# UART_connect.net
KiCad netlist of a schematic drawn in Altium Designer
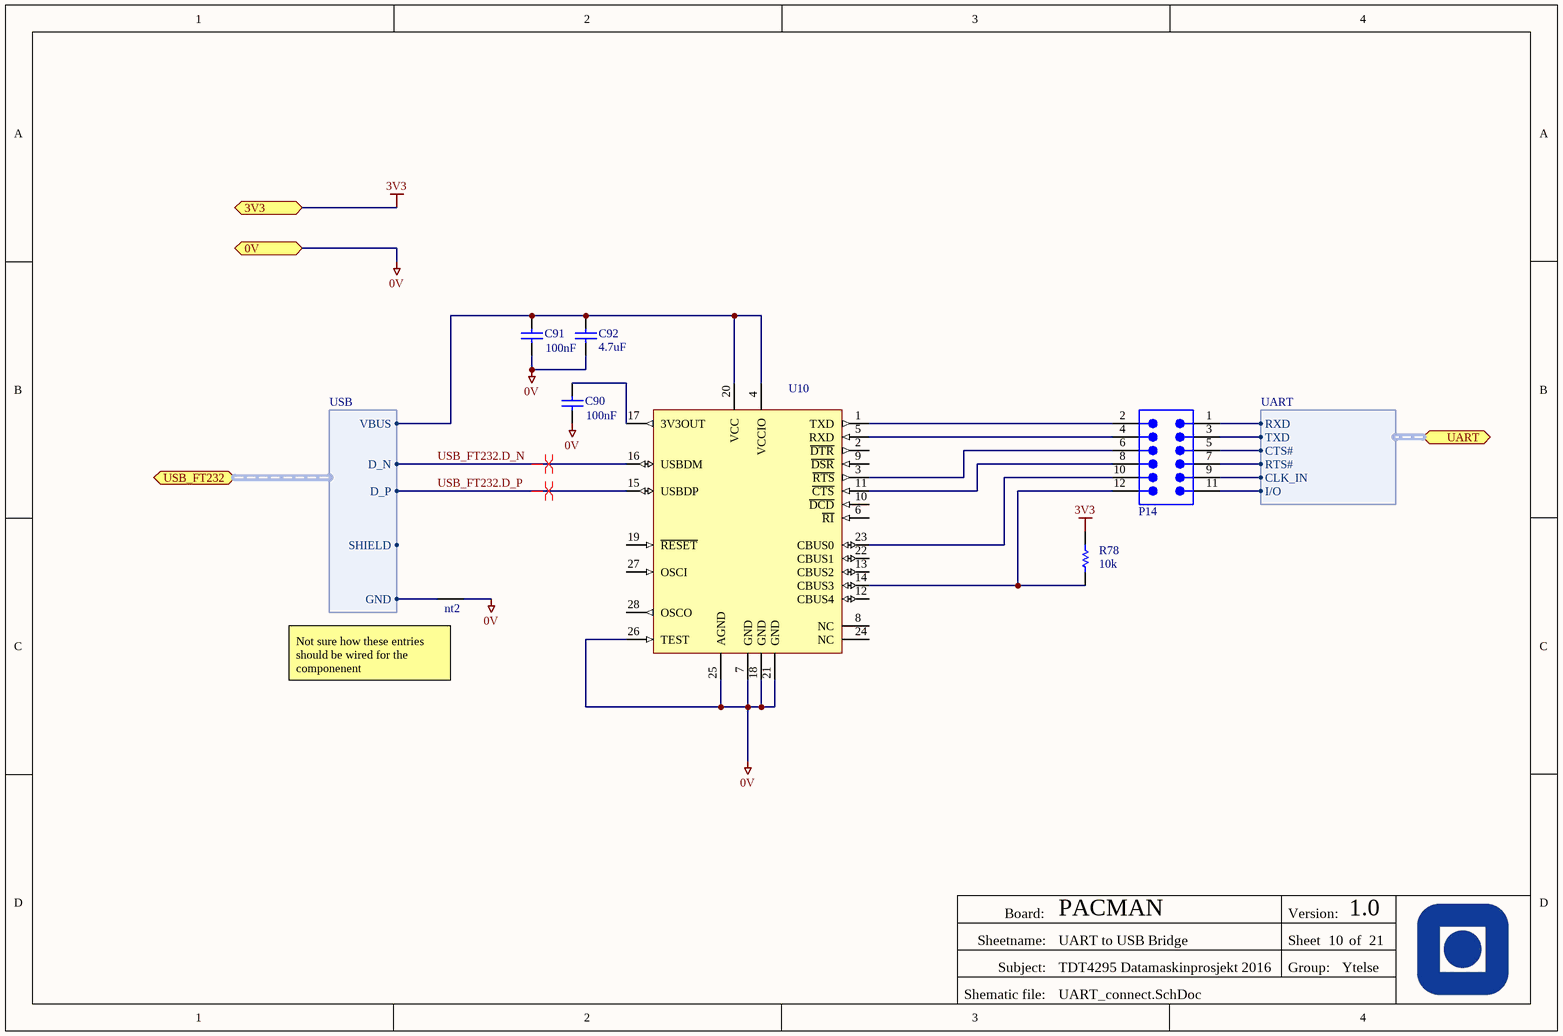
[diagram p0: UART_connect.SchDoc]

(export (version "E")
  (design (tool "Eeschema 10.0.6"))
  (components
    (comp (ref "C90")
      (value "100nF")
      (footprint "CAPC0603(1608)100_M")
      (description "CAP 100nF 16V ±5% 0603 (1608 Metric) Thickness 1mm SMD")
      (fields (field (name "TOLERANCE") "Â±5%") (field (name "Comment") "CAP 100nF 16V 0603(1608)"))
      (libsource (lib "Altium Content Vault") (part "CMP-1035-02583-1"))
    )
    (comp (ref "C91")
      (value "100nF")
      (footprint "CAPC0603(1608)100_M")
      (description "CAP 100nF 16V ±5% 0603 (1608 Metric) Thickness 1mm SMD")
      (fields (field (name "TOLERANCE") "Â±5%") (field (name "Comment") "CAP 100nF 16V 0603(1608)"))
      (libsource (lib "Altium Content Vault") (part "CMP-1035-02583-1"))
    )
    (comp (ref "C92")
      (value "4.7uF")
      (footprint "CAPC0603(1608)100_M")
      (description "CAP 4.7uF 16V ±10% 0603 (1608 Metric) Thickness 1mm SMD")
      (fields (field (name "TOLERANCE") "Â±10%") (field (name "Comment") "CAP 4.7uF 16V 0603(1608)"))
      (libsource (lib "Altium Content Vault") (part "CMP-1035-02788-1"))
    )
    (comp (ref "nt2")
      (value "net tie")
      (footprint "net tie")
      (description "used to connect nets without transferring net name")
      (libsource (lib "dmpro16lib") (part "net tie"))
    )
    (comp (ref "P14")
      (value "TSW-106-07-T-D")
      (footprint "SMTC-TSW-106-07-X-D")
      (fields (field (name "MANUFACTURER") "Samtec"))
      (libsource (lib "Altium Content Vault") (part "CMP-1024-00380-1"))
    )
    (comp (ref "R78")
      (value "10k")
      (footprint "RESC0603(1608)_N")
      (description "10K 0.1W 1% 0603 (1608 Metric)  SMD")
      (fields (field (name "POWER") "0.1 W") (field (name "TOLERANCE") "1 %"))
      (libsource (lib "Altium Content Vault") (part "CMP-1012-00623-1"))
    )
    (comp (ref "U10")
      (value "FT232RL-Reel")
      (footprint "SSOP-28_L")
      (description "USB UART Asynchronous Serial Data Transfer Chip, SSOP-28, Tape and Reel")
      (libsource (lib "Altium Content Vault") (part "CMP-0078-00029-1"))
    )
  )
  (nets
    (net (code "3") (name "/CLK_IN") (class "Default")
      (node (ref "P14") (pin "9") (pinfunction "9_9") (pintype "passive"))
    )
    (net (code "4") (name "/CTS#") (class "Default")
      (node (ref "P14") (pin "5") (pinfunction "5_5") (pintype "passive"))
    )
    (net (code "5") (name "/GND") (class "Default")
      (node (ref "nt2") (pin "0") (pinfunction "0_0") (pintype "passive"))
    )
    (net (code "6") (name "/I{slash}O") (class "Default")
      (node (ref "P14") (pin "11") (pinfunction "11_11") (pintype "passive"))
    )
    (net (code "7") (name "/RTS#") (class "Default")
      (node (ref "P14") (pin "7") (pinfunction "7_7") (pintype "passive"))
    )
    (net (code "8") (name "/RXD") (class "Default")
      (node (ref "P14") (pin "1") (pinfunction "1_1") (pintype "passive"))
    )
    (net (code "9") (name "/TXD") (class "Default")
      (node (ref "P14") (pin "3") (pinfunction "3_3") (pintype "passive"))
    )
    (net (code "10") (name "/USB_FT232.D_N") (class "Default")
      (node (ref "U10") (pin "16") (pinfunction "USBDM_16") (pintype "bidirectional"))
    )
    (net (code "11") (name "/USB_FT232.D_P") (class "Default")
      (node (ref "U10") (pin "15") (pinfunction "USBDP_15") (pintype "bidirectional"))
    )
    (net (code "12") (name "/VBUS") (class "Default")
      (node (ref "C91") (pin "2") (pinfunction "2_2") (pintype "passive"))
      (node (ref "C92") (pin "2") (pinfunction "2_2") (pintype "passive"))
      (node (ref "U10") (pin "20") (pinfunction "VCC_20") (pintype "power_in"))
      (node (ref "U10") (pin "4") (pinfunction "VCCIO_4") (pintype "power_in"))
    )
    (net (code "15") (name "0V") (class "Default")
      (node (ref "C90") (pin "1") (pinfunction "1_1") (pintype "passive"))
      (node (ref "C91") (pin "1") (pinfunction "1_1") (pintype "passive"))
      (node (ref "C92") (pin "1") (pinfunction "1_1") (pintype "passive"))
      (node (ref "U10") (pin "18") (pinfunction "GND_18") (pintype "power_in"))
      (node (ref "U10") (pin "21") (pinfunction "GND_21") (pintype "power_in"))
      (node (ref "U10") (pin "25") (pinfunction "AGND_25") (pintype "power_in"))
      (node (ref "U10") (pin "26") (pinfunction "TEST_26") (pintype "input"))
      (node (ref "U10") (pin "7") (pinfunction "GND_7") (pintype "power_in"))
      (node (ref "nt2") (pin "1") (pinfunction "1_1") (pintype "passive"))
    )
    (net (code "16") (name "3V3") (class "Default")
      (node (ref "R78") (pin "2") (pinfunction "2_2") (pintype "passive"))
    )
    (net (code "17") (name "Net-(U10-3V3OUT)") (class "Default")
      (node (ref "C90") (pin "2") (pinfunction "2_2") (pintype "passive"))
      (node (ref "U10") (pin "17") (pinfunction "3V3OUT_17") (pintype "output"))
    )
    (net (code "18") (name "Net-(U10-CBUS0)") (class "Default")
      (node (ref "P14") (pin "10") (pinfunction "10_10") (pintype "passive"))
      (node (ref "U10") (pin "23") (pinfunction "CBUS0_23") (pintype "bidirectional"))
    )
    (net (code "19") (name "Net-(U10-CBUS3)") (class "Default")
      (node (ref "P14") (pin "12") (pinfunction "12_12") (pintype "passive"))
      (node (ref "R78") (pin "1") (pinfunction "1_1") (pintype "passive"))
      (node (ref "U10") (pin "14") (pinfunction "CBUS3_14") (pintype "bidirectional"))
    )
    (net (code "20") (name "Net-(U10-RXD)") (class "Default")
      (node (ref "P14") (pin "4") (pinfunction "4_4") (pintype "passive"))
      (node (ref "U10") (pin "5") (pinfunction "RXD_5") (pintype "input"))
    )
    (net (code "21") (name "Net-(U10-TXD)") (class "Default")
      (node (ref "P14") (pin "2") (pinfunction "2_2") (pintype "passive"))
      (node (ref "U10") (pin "1") (pinfunction "TXD_1") (pintype "output"))
    )
    (net (code "22") (name "Net-(U10-~{CTS})") (class "Default")
      (node (ref "P14") (pin "8") (pinfunction "8_8") (pintype "passive"))
      (node (ref "U10") (pin "11") (pinfunction "~{CTS}_11") (pintype "input"))
    )
    (net (code "23") (name "Net-(U10-~{RTS})") (class "Default")
      (node (ref "P14") (pin "6") (pinfunction "6_6") (pintype "passive"))
      (node (ref "U10") (pin "3") (pinfunction "~{RTS}_3") (pintype "output"))
    )
    (net (code "24") (name "unconnected-(U10-CBUS1-Pad22)") (class "Default")
      (node (ref "U10") (pin "22") (pinfunction "CBUS1_22") (pintype "bidirectional"))
    )
    (net (code "25") (name "unconnected-(U10-CBUS2-Pad13)") (class "Default")
      (node (ref "U10") (pin "13") (pinfunction "CBUS2_13") (pintype "bidirectional"))
    )
    (net (code "26") (name "unconnected-(U10-CBUS4-Pad12)") (class "Default")
      (node (ref "U10") (pin "12") (pinfunction "CBUS4_12") (pintype "bidirectional"))
    )
    (net (code "27") (name "unconnected-(U10-NC-Pad8)") (class "Default")
      (node (ref "U10") (pin "8") (pinfunction "NC_8") (pintype "passive"))
    )
    (net (code "28") (name "unconnected-(U10-NC-Pad24)") (class "Default")
      (node (ref "U10") (pin "24") (pinfunction "NC_24") (pintype "passive"))
    )
    (net (code "29") (name "unconnected-(U10-OSCI-Pad27)") (class "Default")
      (node (ref "U10") (pin "27") (pinfunction "OSCI_27") (pintype "input"))
    )
    (net (code "30") (name "unconnected-(U10-OSCO-Pad28)") (class "Default")
      (node (ref "U10") (pin "28") (pinfunction "OSCO_28") (pintype "output"))
    )
    (net (code "31") (name "unconnected-(U10-~{DCD}-Pad10)") (class "Default")
      (node (ref "U10") (pin "10") (pinfunction "~{DCD}_10") (pintype "input"))
    )
    (net (code "32") (name "unconnected-(U10-~{DSR}-Pad9)") (class "Default")
      (node (ref "U10") (pin "9") (pinfunction "~{DSR}_9") (pintype "input"))
    )
    (net (code "33") (name "unconnected-(U10-~{DTR}-Pad2)") (class "Default")
      (node (ref "U10") (pin "2") (pinfunction "~{DTR}_2") (pintype "output"))
    )
    (net (code "34") (name "unconnected-(U10-~{RESET}-Pad19)") (class "Default")
      (node (ref "U10") (pin "19") (pinfunction "~{RESET}_19") (pintype "input"))
    )
    (net (code "35") (name "unconnected-(U10-~{RI}-Pad6)") (class "Default")
      (node (ref "U10") (pin "6") (pinfunction "~{RI}_6") (pintype "input"))
    )
  )
)
